# Sheet2.net
KiCad netlist of a schematic drawn in Altium Designer
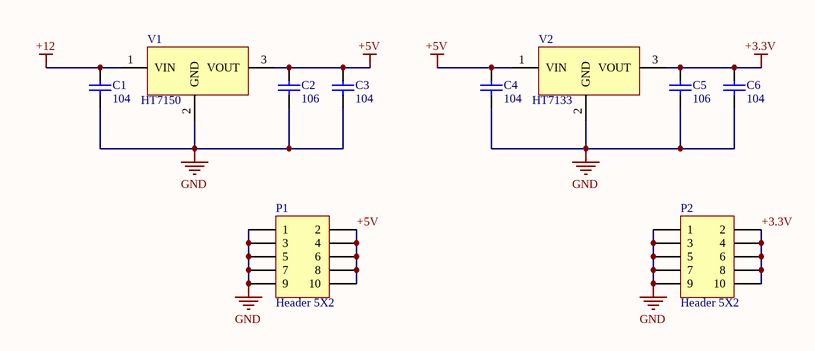
[diagram p0: Sheet2.SchDoc]

(export (version "E")
  (design (tool "Eeschema 10.0.6"))
  (components
    (comp (ref "C1")
      (value "104")
      (footprint "C 0805_M")
      (description "Capacitor")
      (fields (field (name "PUBLISHER") "Altium Limited"))
      (libsource (lib "STM32F103C8T6") (part "Cap"))
    )
    (comp (ref "C2")
      (value "106")
      (footprint "C 0805_M")
      (description "Capacitor")
      (fields (field (name "PUBLISHER") "Altium Limited"))
      (libsource (lib "STM32F103C8T6") (part "Cap"))
    )
    (comp (ref "C3")
      (value "104")
      (footprint "C 0805_M")
      (description "Capacitor")
      (fields (field (name "PUBLISHER") "Altium Limited"))
      (libsource (lib "STM32F103C8T6") (part "Cap"))
    )
    (comp (ref "C4")
      (value "104")
      (footprint "C 0805_M")
      (description "Capacitor")
      (fields (field (name "PUBLISHER") "Altium Limited"))
      (libsource (lib "STM32F103C8T6") (part "Cap"))
    )
    (comp (ref "C5")
      (value "106")
      (footprint "C 0805_M")
      (description "Capacitor")
      (fields (field (name "PUBLISHER") "Altium Limited"))
      (libsource (lib "STM32F103C8T6") (part "Cap"))
    )
    (comp (ref "C6")
      (value "104")
      (footprint "C 0805_M")
      (description "Capacitor")
      (fields (field (name "PUBLISHER") "Altium Limited"))
      (libsource (lib "STM32F103C8T6") (part "Cap"))
    )
    (comp (ref "P1")
      (value "Header 5X2")
      (footprint "HDR2.54-LI-2x5P")
      (description "Header, 5-Pin, Dual row")
      (fields (field (name "PUBLISHER") "Altium Limited"))
      (libsource (lib "Miscellaneous Connectors") (part "Header 5X2"))
    )
    (comp (ref "P2")
      (value "Header 5X2")
      (footprint "HDR2.54-LI-2x5P")
      (description "Header, 5-Pin, Dual row")
      (fields (field (name "PUBLISHER") "Altium Limited"))
      (libsource (lib "Miscellaneous Connectors") (part "Header 5X2"))
    )
    (comp (ref "V1")
      (value "HT7150")
      (footprint "TO220A")
      (description "线性稳压芯片")
      (fields (field (name "版权归属") "源创客"))
      (libsource (lib "1.3   - 电源类芯片") (part "78xx"))
    )
    (comp (ref "V2")
      (value "HT7133")
      (footprint "TO220A")
      (description "线性稳压芯片")
      (fields (field (name "版权归属") "源创客"))
      (libsource (lib "1.3   - 电源类芯片") (part "78xx"))
    )
  )
  (nets
    (net (code "1") (name "+3.3V") (class "Default")
      (node (ref "C5") (pin "1") (pinfunction "1_1") (pintype "passive"))
      (node (ref "C6") (pin "1") (pinfunction "1_1") (pintype "passive"))
      (node (ref "P2") (pin "10") (pinfunction "10_10") (pintype "passive"))
      (node (ref "P2") (pin "2") (pinfunction "2_2") (pintype "passive"))
      (node (ref "P2") (pin "4") (pinfunction "4_4") (pintype "passive"))
      (node (ref "P2") (pin "6") (pinfunction "6_6") (pintype "passive"))
      (node (ref "P2") (pin "8") (pinfunction "8_8") (pintype "passive"))
      (node (ref "V2") (pin "3") (pinfunction "VOUT_3") (pintype "passive"))
    )
    (net (code "2") (name "+5V") (class "Default")
      (node (ref "C2") (pin "1") (pinfunction "1_1") (pintype "passive"))
      (node (ref "C3") (pin "1") (pinfunction "1_1") (pintype "passive"))
      (node (ref "C4") (pin "1") (pinfunction "1_1") (pintype "passive"))
      (node (ref "P1") (pin "10") (pinfunction "10_10") (pintype "passive"))
      (node (ref "P1") (pin "2") (pinfunction "2_2") (pintype "passive"))
      (node (ref "P1") (pin "4") (pinfunction "4_4") (pintype "passive"))
      (node (ref "P1") (pin "6") (pinfunction "6_6") (pintype "passive"))
      (node (ref "P1") (pin "8") (pinfunction "8_8") (pintype "passive"))
      (node (ref "V1") (pin "3") (pinfunction "VOUT_3") (pintype "passive"))
      (node (ref "V2") (pin "1") (pinfunction "VIN_1") (pintype "passive"))
    )
    (net (code "3") (name "+12") (class "Default")
      (node (ref "C1") (pin "1") (pinfunction "1_1") (pintype "passive"))
      (node (ref "V1") (pin "1") (pinfunction "VIN_1") (pintype "passive"))
    )
    (net (code "4") (name "GND") (class "Default")
      (node (ref "C1") (pin "2") (pinfunction "2_2") (pintype "passive"))
      (node (ref "C2") (pin "2") (pinfunction "2_2") (pintype "passive"))
      (node (ref "C3") (pin "2") (pinfunction "2_2") (pintype "passive"))
      (node (ref "C4") (pin "2") (pinfunction "2_2") (pintype "passive"))
      (node (ref "C5") (pin "2") (pinfunction "2_2") (pintype "passive"))
      (node (ref "C6") (pin "2") (pinfunction "2_2") (pintype "passive"))
      (node (ref "P1") (pin "1") (pinfunction "1_1") (pintype "passive"))
      (node (ref "P1") (pin "3") (pinfunction "3_3") (pintype "passive"))
      (node (ref "P1") (pin "5") (pinfunction "5_5") (pintype "passive"))
      (node (ref "P1") (pin "7") (pinfunction "7_7") (pintype "passive"))
      (node (ref "P1") (pin "9") (pinfunction "9_9") (pintype "passive"))
      (node (ref "P2") (pin "1") (pinfunction "1_1") (pintype "passive"))
      (node (ref "P2") (pin "3") (pinfunction "3_3") (pintype "passive"))
      (node (ref "P2") (pin "5") (pinfunction "5_5") (pintype "passive"))
      (node (ref "P2") (pin "7") (pinfunction "7_7") (pintype "passive"))
      (node (ref "P2") (pin "9") (pinfunction "9_9") (pintype "passive"))
      (node (ref "V1") (pin "2") (pinfunction "GND_2") (pintype "passive"))
      (node (ref "V2") (pin "2") (pinfunction "GND_2") (pintype "passive"))
    )
  )
)
